# MCU.net
KiCad netlist of a schematic drawn in Altium Designer
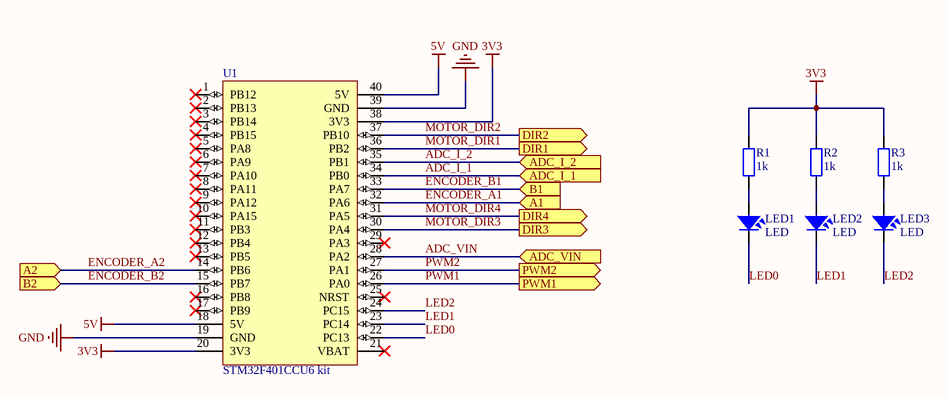
[diagram p0: MCU.SchDoc]

(export (version "E")
  (design (tool "Eeschema 10.0.6"))
  (components
    (comp (ref "LED1")
      (value "LED")
      (footprint "LED-0805-Red")
      (description "LED Single colour Green and Red")
      (libsource (lib "My Library") (part "LED"))
    )
    (comp (ref "LED2")
      (value "LED")
      (footprint "LED-0805-Orange")
      (description "LED Single colour Green and Red")
      (libsource (lib "My Library") (part "LED"))
    )
    (comp (ref "LED3")
      (value "LED")
      (footprint "LED-0805-Green")
      (description "LED Single colour Green and Red")
      (libsource (lib "My Library") (part "LED"))
    )
    (comp (ref "R1")
      (value "1k")
      (footprint "RES-SMD-0805")
      (description "Resistor SMD")
      (fields
        (field (name "MANUFACTURER") "Generic Components")
        (field (name "PUBLISHER") "Altium Hobart Technology Centre")
      )
      (libsource (lib "My Library") (part "Resistor - SMD"))
    )
    (comp (ref "R2")
      (value "1k")
      (footprint "RES-SMD-0805")
      (description "Resistor SMD")
      (fields
        (field (name "MANUFACTURER") "Generic Components")
        (field (name "PUBLISHER") "Altium Hobart Technology Centre")
      )
      (libsource (lib "My Library") (part "Resistor - SMD"))
    )
    (comp (ref "R3")
      (value "1k")
      (footprint "RES-SMD-0805")
      (description "Resistor SMD")
      (fields
        (field (name "MANUFACTURER") "Generic Components")
        (field (name "PUBLISHER") "Altium Hobart Technology Centre")
      )
      (libsource (lib "My Library") (part "Resistor - SMD"))
    )
    (comp (ref "U1")
      (value "STM32F401CCU6 kit")
      (footprint "STM32F401 KIT")
      (description "STM32F401CCU6 breakout board. STM32 ARM-based 32-bit MCU")
      (libsource (lib "My Library") (part "STM32F401CCU6"))
    )
  )
  (nets
    (net (code "1") (name "/ADC_I_1") (class "Default")
      (node (ref "U1") (pin "34") (pinfunction "PB0_34") (pintype "bidirectional"))
    )
    (net (code "2") (name "/ADC_I_2") (class "Default")
      (node (ref "U1") (pin "35") (pinfunction "PB1_35") (pintype "bidirectional"))
    )
    (net (code "3") (name "/ADC_VIN") (class "Default")
      (node (ref "U1") (pin "28") (pinfunction "PA2_28") (pintype "bidirectional"))
    )
    (net (code "4") (name "/ENCODER_A1") (class "Default")
      (node (ref "U1") (pin "32") (pinfunction "PA6_32") (pintype "bidirectional"))
    )
    (net (code "5") (name "/ENCODER_A2") (class "Default")
      (node (ref "U1") (pin "14") (pinfunction "PB6_14") (pintype "bidirectional"))
    )
    (net (code "6") (name "/ENCODER_B1") (class "Default")
      (node (ref "U1") (pin "33") (pinfunction "PA7_33") (pintype "bidirectional"))
    )
    (net (code "7") (name "/ENCODER_B2") (class "Default")
      (node (ref "U1") (pin "15") (pinfunction "PB7_15") (pintype "bidirectional"))
    )
    (net (code "8") (name "/LED0") (class "Default")
      (node (ref "LED1") (pin "2") (pinfunction "2_2") (pintype "passive"))
      (node (ref "U1") (pin "22") (pinfunction "PC13_22") (pintype "bidirectional"))
    )
    (net (code "9") (name "/LED1") (class "Default")
      (node (ref "LED2") (pin "2") (pinfunction "2_2") (pintype "passive"))
      (node (ref "U1") (pin "23") (pinfunction "PC14_23") (pintype "bidirectional"))
    )
    (net (code "10") (name "/LED2") (class "Default")
      (node (ref "LED3") (pin "2") (pinfunction "2_2") (pintype "passive"))
      (node (ref "U1") (pin "24") (pinfunction "PC15_24") (pintype "bidirectional"))
    )
    (net (code "11") (name "/MOTOR_DIR1") (class "Default")
      (node (ref "U1") (pin "36") (pinfunction "PB2_36") (pintype "bidirectional"))
    )
    (net (code "12") (name "/MOTOR_DIR2") (class "Default")
      (node (ref "U1") (pin "37") (pinfunction "PB10_37") (pintype "bidirectional"))
    )
    (net (code "13") (name "/MOTOR_DIR3") (class "Default")
      (node (ref "U1") (pin "30") (pinfunction "PA4_30") (pintype "bidirectional"))
    )
    (net (code "14") (name "/MOTOR_DIR4") (class "Default")
      (node (ref "U1") (pin "31") (pinfunction "PA5_31") (pintype "bidirectional"))
    )
    (net (code "15") (name "/PWM1") (class "Default")
      (node (ref "U1") (pin "26") (pinfunction "PA0_26") (pintype "bidirectional"))
    )
    (net (code "16") (name "/PWM2") (class "Default")
      (node (ref "U1") (pin "27") (pinfunction "PA1_27") (pintype "bidirectional"))
    )
    (net (code "17") (name "3V3") (class "Default")
      (node (ref "R1") (pin "1") (pinfunction "1_1") (pintype "passive"))
      (node (ref "R2") (pin "1") (pinfunction "1_1") (pintype "passive"))
      (node (ref "R3") (pin "1") (pinfunction "1_1") (pintype "passive"))
      (node (ref "U1") (pin "20") (pinfunction "3V3_20") (pintype "power_in"))
      (node (ref "U1") (pin "38") (pinfunction "3V3_38") (pintype "power_in"))
    )
    (net (code "18") (name "5V") (class "Default")
      (node (ref "U1") (pin "18") (pinfunction "5V_18") (pintype "power_in"))
      (node (ref "U1") (pin "40") (pinfunction "5V_40") (pintype "power_in"))
    )
    (net (code "19") (name "GND") (class "Default")
      (node (ref "U1") (pin "19") (pinfunction "GND_19") (pintype "power_in"))
      (node (ref "U1") (pin "39") (pinfunction "GND_39") (pintype "power_in"))
    )
    (net (code "20") (name "Net-(LED1-Pad1)") (class "Default")
      (node (ref "LED1") (pin "1") (pinfunction "1_1") (pintype "passive"))
      (node (ref "R1") (pin "2") (pinfunction "2_2") (pintype "passive"))
    )
    (net (code "21") (name "Net-(LED2-Pad1)") (class "Default")
      (node (ref "LED2") (pin "1") (pinfunction "1_1") (pintype "passive"))
      (node (ref "R2") (pin "2") (pinfunction "2_2") (pintype "passive"))
    )
    (net (code "22") (name "Net-(LED3-Pad1)") (class "Default")
      (node (ref "LED3") (pin "1") (pinfunction "1_1") (pintype "passive"))
      (node (ref "R3") (pin "2") (pinfunction "2_2") (pintype "passive"))
    )
    (net (code "23") (name "unconnected-(U1-NRST-Pad25)") (class "Default")
      (node (ref "U1") (pin "25") (pinfunction "NRST_25") (pintype "bidirectional+no_connect"))
    )
    (net (code "24") (name "unconnected-(U1-PA3-Pad29)") (class "Default")
      (node (ref "U1") (pin "29") (pinfunction "PA3_29") (pintype "bidirectional+no_connect"))
    )
    (net (code "25") (name "unconnected-(U1-PA8-Pad5)") (class "Default")
      (node (ref "U1") (pin "5") (pinfunction "PA8_5") (pintype "bidirectional+no_connect"))
    )
    (net (code "26") (name "unconnected-(U1-PA9-Pad6)") (class "Default")
      (node (ref "U1") (pin "6") (pinfunction "PA9_6") (pintype "bidirectional+no_connect"))
    )
    (net (code "27") (name "unconnected-(U1-PA10-Pad7)") (class "Default")
      (node (ref "U1") (pin "7") (pinfunction "PA10_7") (pintype "bidirectional+no_connect"))
    )
    (net (code "28") (name "unconnected-(U1-PA11-Pad8)") (class "Default")
      (node (ref "U1") (pin "8") (pinfunction "PA11_8") (pintype "bidirectional+no_connect"))
    )
    (net (code "29") (name "unconnected-(U1-PA12-Pad9)") (class "Default")
      (node (ref "U1") (pin "9") (pinfunction "PA12_9") (pintype "bidirectional+no_connect"))
    )
    (net (code "30") (name "unconnected-(U1-PA15-Pad10)") (class "Default")
      (node (ref "U1") (pin "10") (pinfunction "PA15_10") (pintype "bidirectional+no_connect"))
    )
    (net (code "31") (name "unconnected-(U1-PB3-Pad11)") (class "Default")
      (node (ref "U1") (pin "11") (pinfunction "PB3_11") (pintype "bidirectional+no_connect"))
    )
    (net (code "32") (name "unconnected-(U1-PB4-Pad12)") (class "Default")
      (node (ref "U1") (pin "12") (pinfunction "PB4_12") (pintype "bidirectional+no_connect"))
    )
    (net (code "33") (name "unconnected-(U1-PB5-Pad13)") (class "Default")
      (node (ref "U1") (pin "13") (pinfunction "PB5_13") (pintype "bidirectional+no_connect"))
    )
    (net (code "34") (name "unconnected-(U1-PB8-Pad16)") (class "Default")
      (node (ref "U1") (pin "16") (pinfunction "PB8_16") (pintype "bidirectional+no_connect"))
    )
    (net (code "35") (name "unconnected-(U1-PB9-Pad17)") (class "Default")
      (node (ref "U1") (pin "17") (pinfunction "PB9_17") (pintype "bidirectional+no_connect"))
    )
    (net (code "36") (name "unconnected-(U1-PB12-Pad1)") (class "Default")
      (node (ref "U1") (pin "1") (pinfunction "PB12_1") (pintype "bidirectional+no_connect"))
    )
    (net (code "37") (name "unconnected-(U1-PB13-Pad2)") (class "Default")
      (node (ref "U1") (pin "2") (pinfunction "PB13_2") (pintype "bidirectional+no_connect"))
    )
    (net (code "38") (name "unconnected-(U1-PB14-Pad3)") (class "Default")
      (node (ref "U1") (pin "3") (pinfunction "PB14_3") (pintype "bidirectional+no_connect"))
    )
    (net (code "39") (name "unconnected-(U1-PB15-Pad4)") (class "Default")
      (node (ref "U1") (pin "4") (pinfunction "PB15_4") (pintype "bidirectional+no_connect"))
    )
    (net (code "40") (name "unconnected-(U1-VBAT-Pad21)") (class "Default")
      (node (ref "U1") (pin "21") (pinfunction "VBAT_21") (pintype "power_in+no_connect"))
    )
  )
)
